# ESC.net
KiCad netlist of a schematic drawn in Altium Designer
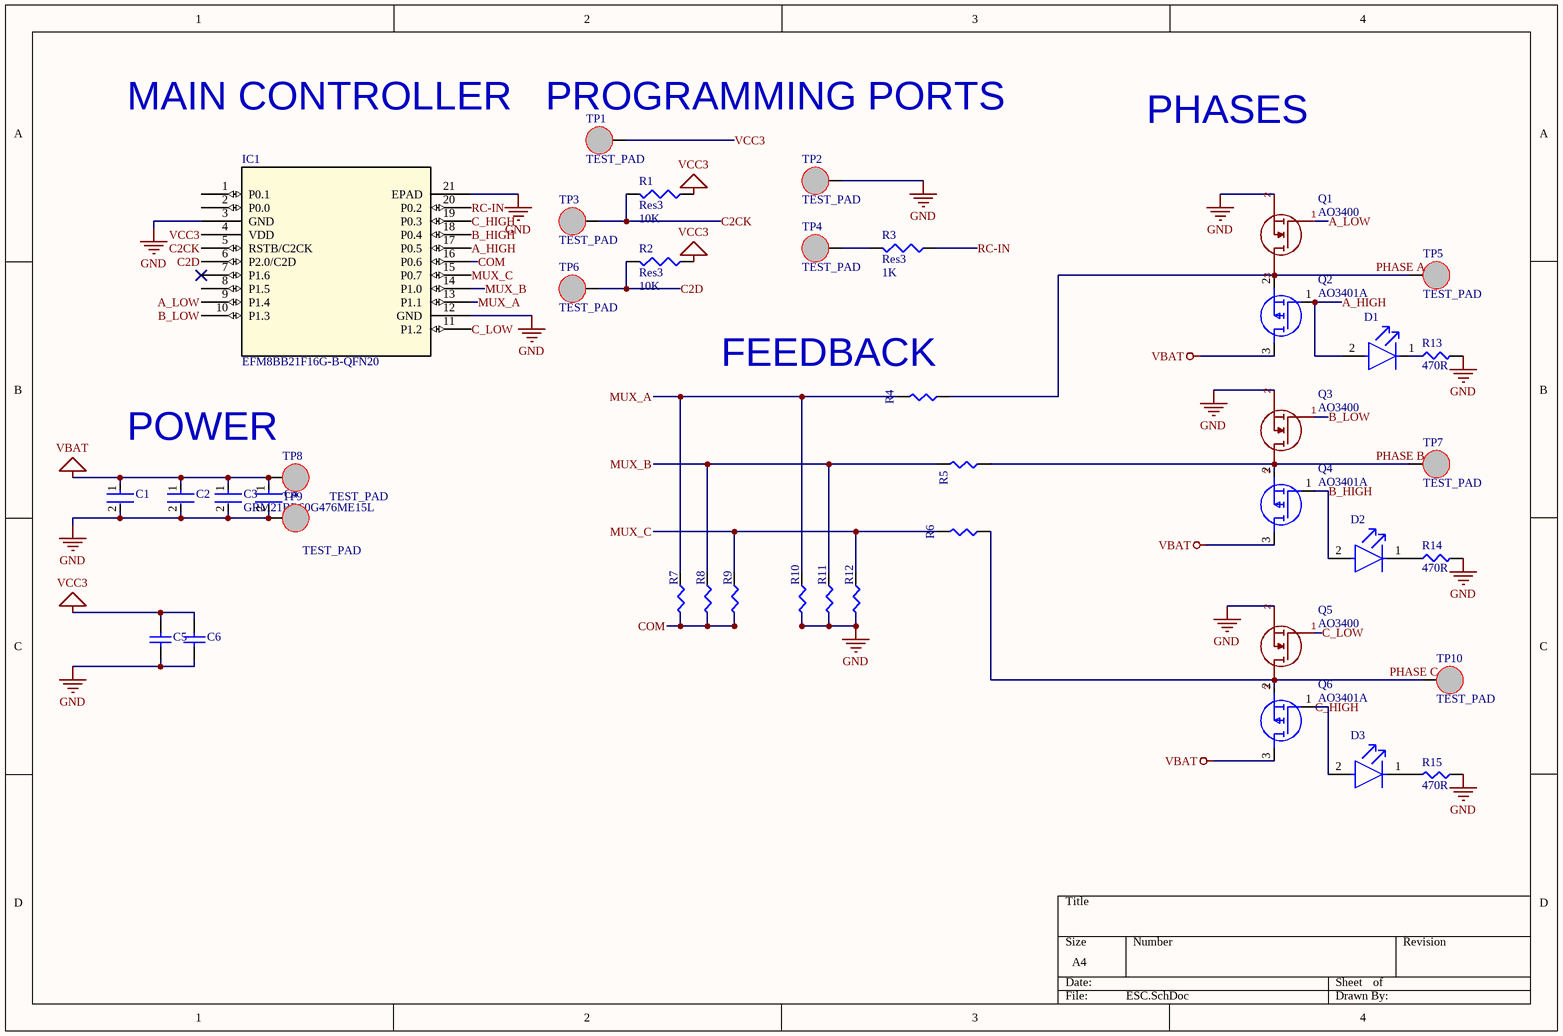
[diagram p0: ESC.SchDoc]

(export (version "E")
  (design (tool "Eeschema 10.0.6"))
  (components
    (comp (ref "C1")
      (value "GRM21BR60G476ME15L")
      (footprint "FP-GRM21B-0_2-IPC_C")
      (description "CAP CER 47UF 4V X5R 0805")
      (fields (field (name "TOLERANCE") "20%") (field (name "VOLTAGE") "4V"))
      (libsource (lib "Altium Content Vault") (part "11868f565c42a9108669ba33697ecf6"))
    )
    (comp (ref "C2")
      (value "GRM21BR60G476ME15L")
      (footprint "FP-GRM21B-0_2-IPC_C")
      (description "CAP CER 47UF 4V X5R 0805")
      (fields (field (name "TOLERANCE") "20%") (field (name "VOLTAGE") "4V"))
      (libsource (lib "Altium Content Vault") (part "11868f565c42a9108669ba33697ecf6"))
    )
    (comp (ref "C3")
      (value "GRM21BR60G476ME15L")
      (footprint "FP-GRM21B-0_2-IPC_C")
      (description "CAP CER 47UF 4V X5R 0805")
      (fields (field (name "TOLERANCE") "20%") (field (name "VOLTAGE") "4V"))
      (libsource (lib "Altium Content Vault") (part "11868f565c42a9108669ba33697ecf6"))
    )
    (comp (ref "C4")
      (value "GRM21BR60G476ME15L")
      (footprint "FP-GRM21B-0_2-IPC_C")
      (description "CAP CER 47UF 4V X5R 0805")
      (fields (field (name "TOLERANCE") "20%") (field (name "VOLTAGE") "4V"))
      (libsource (lib "Altium Content Vault") (part "11868f565c42a9108669ba33697ecf6"))
    )
    (comp (ref "C5")
      (value "VJ0603Y104KNXAO")
      (footprint "CAPC1608X92X38LL15T08")
      (fields (field (name "MANUFACTURER") "Vitramon"))
      (libsource (lib "Altium Content Vault") (part "CAP"))
    )
    (comp (ref "C6")
      (value "VJ0603Y104KNXAO")
      (footprint "CAPC1608X92X38LL15T08")
      (fields (field (name "MANUFACTURER") "Vitramon"))
      (libsource (lib "Altium Content Vault") (part "CAP"))
    )
    (comp (ref "D1")
      (value "SML-LX0603IW-TR")
      (footprint "FP-SML-LX0603IW-TR-MFG")
      (description "LED RED DIFFUSED SMD")
      (libsource (lib "Altium Content Vault") (part "8706943c75ba83719d021d2fdc84c58"))
    )
    (comp (ref "D2")
      (value "SML-LX0603IW-TR")
      (footprint "FP-SML-LX0603IW-TR-MFG")
      (description "LED RED DIFFUSED SMD")
      (libsource (lib "Altium Content Vault") (part "8706943c75ba83719d021d2fdc84c58"))
    )
    (comp (ref "D3")
      (value "SML-LX0603IW-TR")
      (footprint "FP-SML-LX0603IW-TR-MFG")
      (description "LED RED DIFFUSED SMD")
      (libsource (lib "Altium Content Vault") (part "8706943c75ba83719d021d2fdc84c58"))
    )
    (comp (ref "IC1")
      (value "EFM8BB21F16G-B-QFN20")
      (footprint "QFN20_3X3_SIL")
      (description "No Description Available")
      (fields (field (name "COPYRIGHT") "Copyright (C) 2023 Ultra Librarian. All rights reserved."))
      (libsource (lib "EFM8BB21F16G-B-QFN20") (part "EFM8BB21F16G-B-QFN20"))
    )
    (comp (ref "Q1")
      (value "AO3400")
      (footprint "SOT-23-3L_AOS-L")
      (libsource (lib "ESC 1s mini") (part "AO3400"))
    )
    (comp (ref "Q2")
      (value "AO3401A")
      (footprint "SOT-23-3L_AOS-L")
      (description "MOSFET (P-Channel)")
      (libsource (lib "*") (part "AO3401A"))
    )
    (comp (ref "Q3")
      (value "AO3400")
      (footprint "SOT-23-3L_AOS-L")
      (libsource (lib "ESC 1s mini") (part "AO3400"))
    )
    (comp (ref "Q4")
      (value "AO3401A")
      (footprint "SOT-23-3L_AOS-L")
      (description "MOSFET (P-Channel)")
      (libsource (lib "*") (part "AO3401A"))
    )
    (comp (ref "Q5")
      (value "AO3400")
      (footprint "SOT-23-3L_AOS-L")
      (libsource (lib "ESC 1s mini") (part "AO3400"))
    )
    (comp (ref "Q6")
      (value "AO3401A")
      (footprint "SOT-23-3L_AOS-L")
      (description "MOSFET (P-Channel)")
      (libsource (lib "*") (part "AO3401A"))
    )
    (comp (ref "R1")
      (value "Res3")
      (footprint "SMD-0603-RES")
      (description "Resistor")
      (fields (field (name "ALTIUM_VALUE") "10K") (field (name "PUBLISHER") "Altium Limited"))
      (libsource (lib "Miscellaneous Devices") (part "Res3"))
    )
    (comp (ref "R2")
      (value "Res3")
      (footprint "SMD-0603-RES")
      (description "Resistor")
      (fields (field (name "ALTIUM_VALUE") "10K") (field (name "PUBLISHER") "Altium Limited"))
      (libsource (lib "Miscellaneous Devices") (part "Res3"))
    )
    (comp (ref "R3")
      (value "Res3")
      (footprint "SMD-0603-RES")
      (description "Resistor")
      (fields (field (name "ALTIUM_VALUE") "1K") (field (name "PUBLISHER") "Altium Limited"))
      (libsource (lib "Miscellaneous Devices") (part "Res3"))
    )
    (comp (ref "R4") (value "~") (footprint "SMD-0603-RES") (libsource (lib "resistors_m") (part "RESISTOR")))
    (comp (ref "R5") (value "~") (footprint "SMD-0603-RES") (libsource (lib "resistors_m") (part "RESISTOR")))
    (comp (ref "R6") (value "~") (footprint "SMD-0603-RES") (libsource (lib "resistors_m") (part "RESISTOR")))
    (comp (ref "R7") (value "~") (footprint "SMD-0603-RES") (libsource (lib "resistors_m") (part "RESISTOR")))
    (comp (ref "R8") (value "~") (footprint "SMD-0603-RES") (libsource (lib "resistors_m") (part "RESISTOR")))
    (comp (ref "R9") (value "~") (footprint "SMD-0603-RES") (libsource (lib "resistors_m") (part "RESISTOR")))
    (comp (ref "R10")
      (value "~")
      (footprint "SMD-0603-RES")
      (libsource (lib "resistors_m") (part "RESISTOR"))
    )
    (comp (ref "R11")
      (value "~")
      (footprint "SMD-0603-RES")
      (libsource (lib "resistors_m") (part "RESISTOR"))
    )
    (comp (ref "R12")
      (value "~")
      (footprint "SMD-0603-RES")
      (libsource (lib "resistors_m") (part "RESISTOR"))
    )
    (comp (ref "R13")
      (value "470R")
      (footprint "SMD-0603-RES")
      (libsource (lib "resistors_m") (part "RESISTOR"))
    )
    (comp (ref "R14")
      (value "470R")
      (footprint "SMD-0603-RES")
      (libsource (lib "resistors_m") (part "RESISTOR"))
    )
    (comp (ref "R15")
      (value "470R")
      (footprint "SMD-0603-RES")
      (libsource (lib "resistors_m") (part "RESISTOR"))
    )
    (comp (ref "TP1")
      (value "TEST_PAD")
      (footprint "PCBComponent_1")
      (libsource (lib "solderpad") (part "TEST_PAD"))
    )
    (comp (ref "TP2")
      (value "TEST_PAD")
      (footprint "PCBComponent_1")
      (libsource (lib "solderpad") (part "TEST_PAD"))
    )
    (comp (ref "TP3")
      (value "TEST_PAD")
      (footprint "PCBComponent_1")
      (libsource (lib "solderpad") (part "TEST_PAD"))
    )
    (comp (ref "TP4")
      (value "TEST_PAD")
      (footprint "PCBComponent_1")
      (libsource (lib "solderpad") (part "TEST_PAD"))
    )
    (comp (ref "TP5")
      (value "TEST_PAD")
      (footprint "PAD_SQUARE")
      (libsource (lib "solderpad") (part "TEST_PAD"))
    )
    (comp (ref "TP6")
      (value "TEST_PAD")
      (footprint "PCBComponent_1")
      (libsource (lib "solderpad") (part "TEST_PAD"))
    )
    (comp (ref "TP7")
      (value "TEST_PAD")
      (footprint "PAD_SQUARE")
      (libsource (lib "solderpad") (part "TEST_PAD"))
    )
    (comp (ref "TP8")
      (value "TEST_PAD")
      (footprint "PAD_SQUARE")
      (libsource (lib "solderpad") (part "TEST_PAD"))
    )
    (comp (ref "TP9")
      (value "TEST_PAD")
      (footprint "PAD_SQUARE")
      (libsource (lib "solderpad") (part "TEST_PAD"))
    )
    (comp (ref "TP10")
      (value "TEST_PAD")
      (footprint "PAD_SQUARE")
      (libsource (lib "solderpad") (part "TEST_PAD"))
    )
  )
  (nets
    (net (code "1") (name "/A_HIGH") (class "Default")
      (node (ref "D1") (pin "2") (pinfunction "A_2") (pintype "passive"))
      (node (ref "IC1") (pin "17") (pinfunction "P0.5_17") (pintype "bidirectional"))
      (node (ref "Q2") (pin "1") (pinfunction "G_1") (pintype "passive"))
    )
    (net (code "2") (name "/A_LOW") (class "Default")
      (node (ref "IC1") (pin "9") (pinfunction "P1.4_9") (pintype "bidirectional"))
      (node (ref "Q1") (pin "1") (pinfunction "1_1") (pintype "passive"))
    )
    (net (code "3") (name "/B_HIGH") (class "Default")
      (node (ref "D2") (pin "2") (pinfunction "A_2") (pintype "passive"))
      (node (ref "IC1") (pin "18") (pinfunction "P0.4_18") (pintype "bidirectional"))
      (node (ref "Q4") (pin "1") (pinfunction "G_1") (pintype "passive"))
    )
    (net (code "4") (name "/B_LOW") (class "Default")
      (node (ref "IC1") (pin "10") (pinfunction "P1.3_10") (pintype "bidirectional"))
      (node (ref "Q3") (pin "1") (pinfunction "1_1") (pintype "passive"))
    )
    (net (code "5") (name "/C2CK") (class "Default")
      (node (ref "IC1") (pin "5") (pinfunction "RSTB/C2CK_5") (pintype "bidirectional"))
      (node (ref "R1") (pin "2") (pinfunction "2_2") (pintype "passive"))
      (node (ref "TP3") (pin "1") (pinfunction "Test_Point_1") (pintype "passive"))
    )
    (net (code "6") (name "/C2D") (class "Default")
      (node (ref "IC1") (pin "6") (pinfunction "P2.0/C2D_6") (pintype "bidirectional"))
      (node (ref "R2") (pin "2") (pinfunction "2_2") (pintype "passive"))
      (node (ref "TP6") (pin "1") (pinfunction "Test_Point_1") (pintype "passive"))
    )
    (net (code "7") (name "/COM") (class "Default")
      (node (ref "IC1") (pin "16") (pinfunction "P0.6_16") (pintype "bidirectional"))
      (node (ref "R7") (pin "2") (pinfunction "2_2") (pintype "passive"))
      (node (ref "R8") (pin "2") (pinfunction "2_2") (pintype "passive"))
      (node (ref "R9") (pin "2") (pinfunction "2_2") (pintype "passive"))
    )
    (net (code "8") (name "/C_HIGH") (class "Default")
      (node (ref "D3") (pin "2") (pinfunction "A_2") (pintype "passive"))
      (node (ref "IC1") (pin "19") (pinfunction "P0.3_19") (pintype "bidirectional"))
      (node (ref "Q6") (pin "1") (pinfunction "G_1") (pintype "passive"))
    )
    (net (code "9") (name "/C_LOW") (class "Default")
      (node (ref "IC1") (pin "11") (pinfunction "P1.2_11") (pintype "bidirectional"))
      (node (ref "Q5") (pin "1") (pinfunction "1_1") (pintype "passive"))
    )
    (net (code "10") (name "/MUX_A") (class "Default")
      (node (ref "IC1") (pin "13") (pinfunction "P1.1_13") (pintype "bidirectional"))
      (node (ref "R10") (pin "1") (pinfunction "1_1") (pintype "passive"))
      (node (ref "R4") (pin "2") (pinfunction "2_2") (pintype "passive"))
      (node (ref "R7") (pin "1") (pinfunction "1_1") (pintype "passive"))
    )
    (net (code "11") (name "/MUX_B") (class "Default")
      (node (ref "IC1") (pin "14") (pinfunction "P1.0_14") (pintype "bidirectional"))
      (node (ref "R11") (pin "1") (pinfunction "1_1") (pintype "passive"))
      (node (ref "R5") (pin "2") (pinfunction "2_2") (pintype "passive"))
      (node (ref "R8") (pin "1") (pinfunction "1_1") (pintype "passive"))
    )
    (net (code "12") (name "/MUX_C") (class "Default")
      (node (ref "IC1") (pin "15") (pinfunction "P0.7_15") (pintype "bidirectional"))
      (node (ref "R12") (pin "1") (pinfunction "1_1") (pintype "passive"))
      (node (ref "R6") (pin "2") (pinfunction "2_2") (pintype "passive"))
      (node (ref "R9") (pin "1") (pinfunction "1_1") (pintype "passive"))
    )
    (net (code "13") (name "/PHASE A") (class "Default")
      (node (ref "Q1") (pin "3") (pinfunction "3_3") (pintype "passive"))
      (node (ref "Q2") (pin "2") (pinfunction "S_2") (pintype "passive"))
      (node (ref "R4") (pin "1") (pinfunction "1_1") (pintype "passive"))
      (node (ref "TP5") (pin "1") (pinfunction "Test_Point_1") (pintype "passive"))
    )
    (net (code "14") (name "/PHASE B") (class "Default")
      (node (ref "Q3") (pin "3") (pinfunction "3_3") (pintype "passive"))
      (node (ref "Q4") (pin "2") (pinfunction "S_2") (pintype "passive"))
      (node (ref "R5") (pin "1") (pinfunction "1_1") (pintype "passive"))
      (node (ref "TP7") (pin "1") (pinfunction "Test_Point_1") (pintype "passive"))
    )
    (net (code "15") (name "/PHASE C") (class "Default")
      (node (ref "Q5") (pin "3") (pinfunction "3_3") (pintype "passive"))
      (node (ref "Q6") (pin "2") (pinfunction "S_2") (pintype "passive"))
      (node (ref "R6") (pin "1") (pinfunction "1_1") (pintype "passive"))
      (node (ref "TP10") (pin "1") (pinfunction "Test_Point_1") (pintype "passive"))
    )
    (net (code "16") (name "/RC-IN") (class "Default")
      (node (ref "IC1") (pin "20") (pinfunction "P0.2_20") (pintype "bidirectional"))
      (node (ref "R3") (pin "1") (pinfunction "1_1") (pintype "passive"))
    )
    (net (code "17") (name "GND") (class "Default")
      (node (ref "C1") (pin "2") (pinfunction "2_2") (pintype "passive"))
      (node (ref "C2") (pin "2") (pinfunction "2_2") (pintype "passive"))
      (node (ref "C3") (pin "2") (pinfunction "2_2") (pintype "passive"))
      (node (ref "C4") (pin "2") (pinfunction "2_2") (pintype "passive"))
      (node (ref "C5") (pin "1") (pinfunction "1_1") (pintype "passive"))
      (node (ref "C6") (pin "1") (pinfunction "1_1") (pintype "passive"))
      (node (ref "IC1") (pin "12") (pinfunction "GND_12") (pintype "power_in"))
      (node (ref "IC1") (pin "21") (pinfunction "EPAD_21") (pintype "passive"))
      (node (ref "IC1") (pin "3") (pinfunction "GND_3") (pintype "power_in"))
      (node (ref "Q1") (pin "2") (pinfunction "2_2") (pintype "passive"))
      (node (ref "Q3") (pin "2") (pinfunction "2_2") (pintype "passive"))
      (node (ref "Q5") (pin "2") (pinfunction "2_2") (pintype "passive"))
      (node (ref "R10") (pin "2") (pinfunction "2_2") (pintype "passive"))
      (node (ref "R11") (pin "2") (pinfunction "2_2") (pintype "passive"))
      (node (ref "R12") (pin "2") (pinfunction "2_2") (pintype "passive"))
      (node (ref "R13") (pin "2") (pinfunction "2_2") (pintype "passive"))
      (node (ref "R14") (pin "2") (pinfunction "2_2") (pintype "passive"))
      (node (ref "R15") (pin "1") (pinfunction "1_1") (pintype "passive"))
      (node (ref "TP2") (pin "1") (pinfunction "Test_Point_1") (pintype "passive"))
      (node (ref "TP9") (pin "1") (pinfunction "Test_Point_1") (pintype "passive"))
    )
    (net (code "18") (name "Net-(D1-C)") (class "Default")
      (node (ref "D1") (pin "1") (pinfunction "C_1") (pintype "passive"))
      (node (ref "R13") (pin "1") (pinfunction "1_1") (pintype "passive"))
    )
    (net (code "19") (name "Net-(D2-C)") (class "Default")
      (node (ref "D2") (pin "1") (pinfunction "C_1") (pintype "passive"))
      (node (ref "R14") (pin "1") (pinfunction "1_1") (pintype "passive"))
    )
    (net (code "20") (name "Net-(D3-C)") (class "Default")
      (node (ref "D3") (pin "1") (pinfunction "C_1") (pintype "passive"))
      (node (ref "R15") (pin "2") (pinfunction "2_2") (pintype "passive"))
    )
    (net (code "21") (name "Net-(TP4-Test_Point)") (class "Default")
      (node (ref "R3") (pin "2") (pinfunction "2_2") (pintype "passive"))
      (node (ref "TP4") (pin "1") (pinfunction "Test_Point_1") (pintype "passive"))
    )
    (net (code "22") (name "VBAT") (class "Default")
      (node (ref "C1") (pin "1") (pinfunction "1_1") (pintype "passive"))
      (node (ref "C2") (pin "1") (pinfunction "1_1") (pintype "passive"))
      (node (ref "C3") (pin "1") (pinfunction "1_1") (pintype "passive"))
      (node (ref "C4") (pin "1") (pinfunction "1_1") (pintype "passive"))
      (node (ref "Q2") (pin "3") (pinfunction "D_3") (pintype "passive"))
      (node (ref "Q4") (pin "3") (pinfunction "D_3") (pintype "passive"))
      (node (ref "Q6") (pin "3") (pinfunction "D_3") (pintype "passive"))
      (node (ref "TP8") (pin "1") (pinfunction "Test_Point_1") (pintype "passive"))
    )
    (net (code "23") (name "VCC3") (class "Default")
      (node (ref "C5") (pin "2") (pinfunction "2_2") (pintype "passive"))
      (node (ref "C6") (pin "2") (pinfunction "2_2") (pintype "passive"))
      (node (ref "IC1") (pin "4") (pinfunction "VDD_4") (pintype "power_in"))
      (node (ref "R1") (pin "1") (pinfunction "1_1") (pintype "passive"))
      (node (ref "R2") (pin "1") (pinfunction "1_1") (pintype "passive"))
      (node (ref "TP1") (pin "1") (pinfunction "Test_Point_1") (pintype "passive"))
    )
    (net (code "24") (name "unconnected-(IC1-P0.0-Pad2)") (class "Default")
      (node (ref "IC1") (pin "2") (pinfunction "P0.0_2") (pintype "bidirectional"))
    )
    (net (code "25") (name "unconnected-(IC1-P0.1-Pad1)") (class "Default")
      (node (ref "IC1") (pin "1") (pinfunction "P0.1_1") (pintype "bidirectional"))
    )
    (net (code "26") (name "unconnected-(IC1-P1.5-Pad8)") (class "Default")
      (node (ref "IC1") (pin "8") (pinfunction "P1.5_8") (pintype "bidirectional"))
    )
    (net (code "27") (name "unconnected-(IC1-P1.6-Pad7)") (class "Default")
      (node (ref "IC1") (pin "7") (pinfunction "P1.6_7") (pintype "bidirectional+no_connect"))
    )
  )
)
